# WSTL18P1.net
KiCad netlist of a schematic drawn in EAGLE
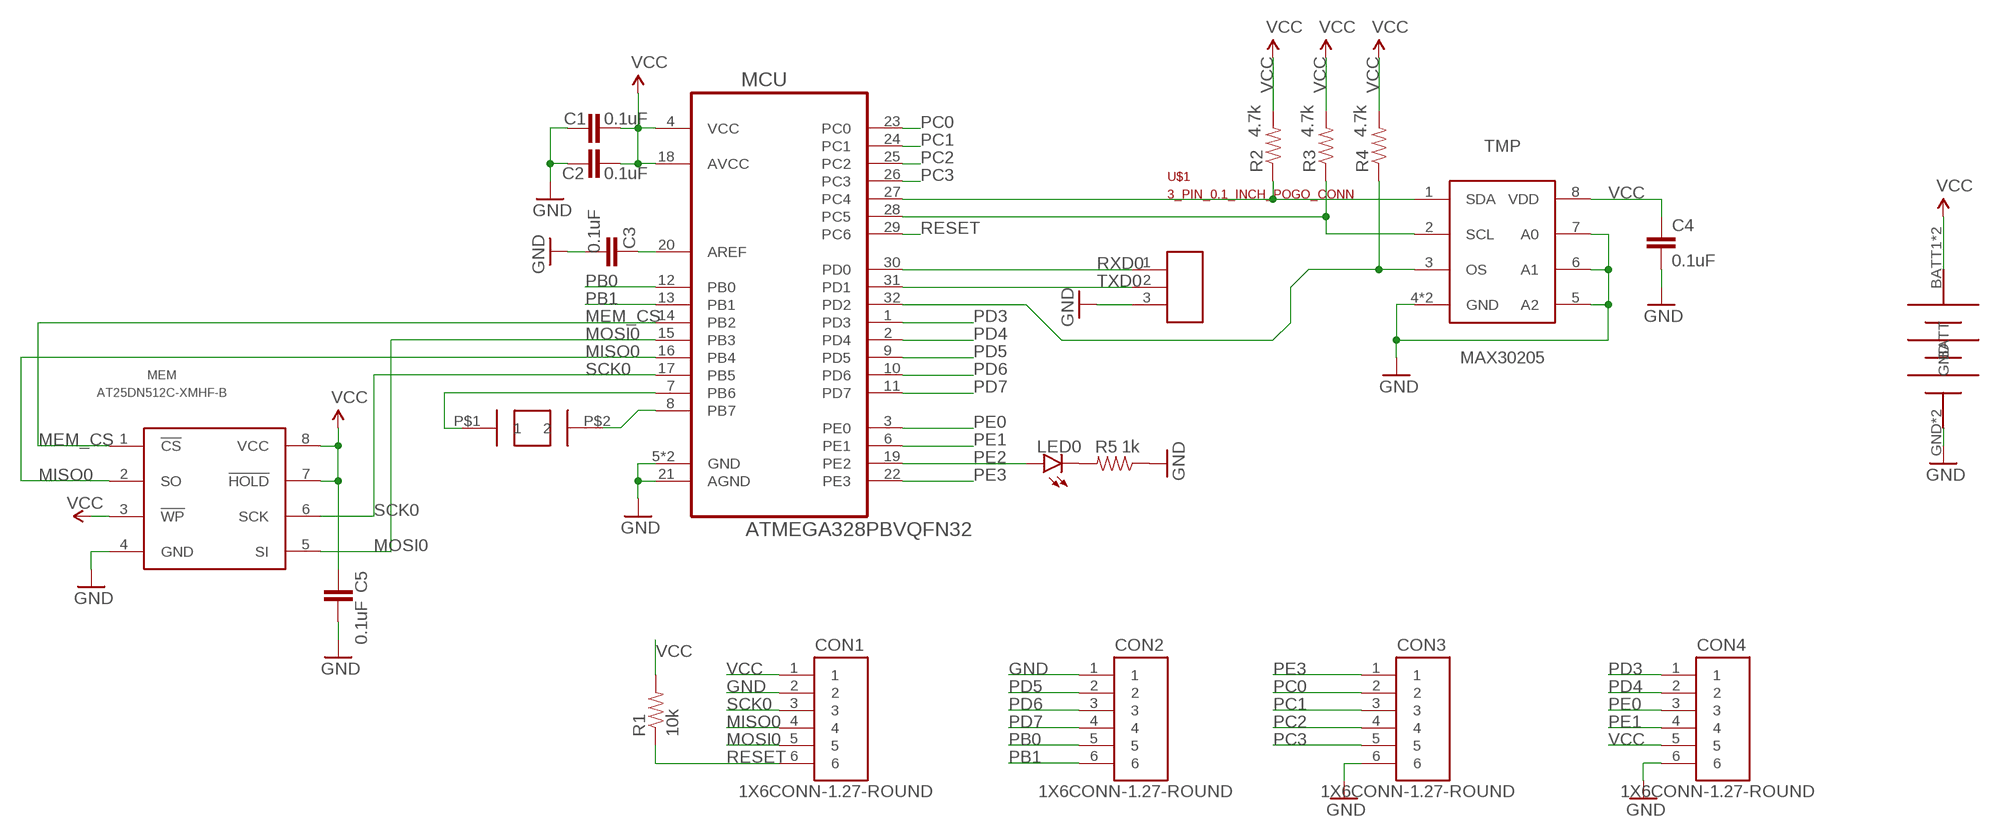
[diagram p0: schematic, sheet 1]

(export (version "E")
  (design (tool "Eeschema 10.0.6"))
  (components
    (comp (ref "BAT")
      (value "LINX-CR2032-BAT-HLD-001-M")
      (footprint "eagle-import:CR2032-LINX-M")
      (libsource (lib "eagle-import") (part "LINX-CR2032-BAT-HLD-001-M"))
    )
    (comp (ref "C1")
      (value "0.1uF")
      (footprint "eagle-import:CAP_0402")
      (libsource (lib "eagle-import") (part "CAP_0402_CERAMIC"))
    )
    (comp (ref "C2")
      (value "0.1uF")
      (footprint "eagle-import:CAP_0402")
      (libsource (lib "eagle-import") (part "CAP_0402_CERAMIC"))
    )
    (comp (ref "C3")
      (value "0.1uF")
      (footprint "eagle-import:CAP_0402")
      (libsource (lib "eagle-import") (part "CAP_0402_CERAMIC"))
    )
    (comp (ref "C4")
      (value "0.1uF")
      (footprint "eagle-import:CAP_0402")
      (libsource (lib "eagle-import") (part "CAP_0402_CERAMIC"))
    )
    (comp (ref "C5")
      (value "0.1uF")
      (footprint "eagle-import:CAP_0402")
      (libsource (lib "eagle-import") (part "CAP_0402_CERAMIC"))
    )
    (comp (ref "CON1")
      (value "1X6CONN-1.27-ROUND")
      (footprint "eagle-import:1X6_1.27_ROUND")
      (libsource (lib "eagle-import") (part "1X6CONN-1.27-ROUND"))
    )
    (comp (ref "CON2")
      (value "1X6CONN-1.27-ROUND")
      (footprint "eagle-import:1X6_1.27_ROUND")
      (libsource (lib "eagle-import") (part "1X6CONN-1.27-ROUND"))
    )
    (comp (ref "CON3")
      (value "1X6CONN-1.27-ROUND")
      (footprint "eagle-import:1X6_1.27_ROUND")
      (libsource (lib "eagle-import") (part "1X6CONN-1.27-ROUND"))
    )
    (comp (ref "CON4")
      (value "1X6CONN-1.27-ROUND")
      (footprint "eagle-import:1X6_1.27_ROUND")
      (libsource (lib "eagle-import") (part "1X6CONN-1.27-ROUND"))
    )
    (comp (ref "LED0")
      (value "LED_0402")
      (footprint "eagle-import:LED_0402")
      (libsource (lib "eagle-import") (part "LED_0402"))
    )
    (comp (ref "MCU")
      (value "ATMEGA328PBVQFN32")
      (footprint "eagle-import:ATMEGA328PB_VFQFN32")
      (libsource (lib "eagle-import") (part "ATMEGA328PBVQFN32"))
    )
    (comp (ref "MEM")
      (value "AT25DN512C-XMHF-B")
      (footprint "eagle-import:TSSSOP-8")
      (libsource (lib "eagle-import") (part "AT25DN512C-XMHF-B"))
    )
    (comp (ref "R1")
      (value "10k")
      (footprint "eagle-import:RES_0402")
      (libsource (lib "eagle-import") (part "RES_0402_CERAMIC"))
    )
    (comp (ref "R2")
      (value "4.7k")
      (footprint "eagle-import:RES_0402")
      (libsource (lib "eagle-import") (part "RES_0402_CERAMIC"))
    )
    (comp (ref "R3")
      (value "4.7k")
      (footprint "eagle-import:RES_0402")
      (libsource (lib "eagle-import") (part "RES_0402_CERAMIC"))
    )
    (comp (ref "R4")
      (value "4.7k")
      (footprint "eagle-import:RES_0402")
      (libsource (lib "eagle-import") (part "RES_0402_CERAMIC"))
    )
    (comp (ref "R5")
      (value "1k")
      (footprint "eagle-import:RES_0402")
      (libsource (lib "eagle-import") (part "RES_0402_CERAMIC"))
    )
    (comp (ref "T1")
      (value "ABS07AIG")
      (footprint "eagle-import:ABS07AIG")
      (libsource (lib "eagle-import") (part "ABS07AIG"))
    )
    (comp (ref "TMP")
      (value "MAX30205")
      (footprint "eagle-import:MAX30205_TDFN8")
      (libsource (lib "eagle-import") (part "MAX30205"))
    )
    (comp (ref "U$1")
      (value "3_PIN_0.1_INCH_POGO_CONN")
      (footprint "eagle-import:3_PIN_0.1INCH_POGO_PADS")
      (libsource (lib "eagle-import") (part "3_PIN_0.1_INCH_POGO_CONN"))
    )
  )
  (nets
    (net (code "1") (name "/MEM_CS") (class "Default")
      (node (ref "MCU") (pin "14") (pinfunction "PB2_14") (pintype "bidirectional"))
      (node (ref "MEM") (pin "1") (pinfunction "~{CS}_1") (pintype "bidirectional"))
    )
    (net (code "2") (name "/MISO0") (class "Default")
      (node (ref "CON1") (pin "4") (pinfunction "4_4") (pintype "bidirectional"))
      (node (ref "MCU") (pin "16") (pinfunction "PB4_16") (pintype "bidirectional"))
      (node (ref "MEM") (pin "2") (pinfunction "SO_2") (pintype "bidirectional"))
    )
    (net (code "3") (name "/MOSI0") (class "Default")
      (node (ref "CON1") (pin "5") (pinfunction "5_5") (pintype "bidirectional"))
      (node (ref "MCU") (pin "15") (pinfunction "PB3_15") (pintype "bidirectional"))
      (node (ref "MEM") (pin "5") (pinfunction "SI_5") (pintype "bidirectional"))
    )
    (net (code "4") (name "/PB0") (class "Default")
      (node (ref "CON2") (pin "5") (pinfunction "5_5") (pintype "bidirectional"))
      (node (ref "MCU") (pin "12") (pinfunction "PB0_12") (pintype "bidirectional"))
    )
    (net (code "5") (name "/PB1") (class "Default")
      (node (ref "CON2") (pin "6") (pinfunction "6_6") (pintype "bidirectional"))
      (node (ref "MCU") (pin "13") (pinfunction "PB1_13") (pintype "bidirectional"))
    )
    (net (code "6") (name "/PC0") (class "Default")
      (node (ref "CON3") (pin "2") (pinfunction "2_2") (pintype "bidirectional"))
      (node (ref "MCU") (pin "23") (pinfunction "PC0_23") (pintype "bidirectional"))
    )
    (net (code "7") (name "/PC1") (class "Default")
      (node (ref "CON3") (pin "3") (pinfunction "3_3") (pintype "bidirectional"))
      (node (ref "MCU") (pin "24") (pinfunction "PC1_24") (pintype "bidirectional"))
    )
    (net (code "8") (name "/PC2") (class "Default")
      (node (ref "CON3") (pin "4") (pinfunction "4_4") (pintype "bidirectional"))
      (node (ref "MCU") (pin "25") (pinfunction "PC2_25") (pintype "bidirectional"))
    )
    (net (code "9") (name "/PC3") (class "Default")
      (node (ref "CON3") (pin "5") (pinfunction "5_5") (pintype "bidirectional"))
      (node (ref "MCU") (pin "26") (pinfunction "PC3_26") (pintype "bidirectional"))
    )
    (net (code "10") (name "/PD3") (class "Default")
      (node (ref "CON4") (pin "1") (pinfunction "1_1") (pintype "bidirectional"))
      (node (ref "MCU") (pin "1") (pinfunction "PD3_1") (pintype "bidirectional"))
    )
    (net (code "11") (name "/PD4") (class "Default")
      (node (ref "CON4") (pin "2") (pinfunction "2_2") (pintype "bidirectional"))
      (node (ref "MCU") (pin "2") (pinfunction "PD4_2") (pintype "bidirectional"))
    )
    (net (code "12") (name "/PD5") (class "Default")
      (node (ref "CON2") (pin "2") (pinfunction "2_2") (pintype "bidirectional"))
      (node (ref "MCU") (pin "9") (pinfunction "PD5_9") (pintype "bidirectional"))
    )
    (net (code "13") (name "/PD6") (class "Default")
      (node (ref "CON2") (pin "3") (pinfunction "3_3") (pintype "bidirectional"))
      (node (ref "MCU") (pin "10") (pinfunction "PD6_10") (pintype "bidirectional"))
    )
    (net (code "14") (name "/PD7") (class "Default")
      (node (ref "CON2") (pin "4") (pinfunction "4_4") (pintype "bidirectional"))
      (node (ref "MCU") (pin "11") (pinfunction "PD7_11") (pintype "bidirectional"))
    )
    (net (code "15") (name "/PE0") (class "Default")
      (node (ref "CON4") (pin "3") (pinfunction "3_3") (pintype "bidirectional"))
      (node (ref "MCU") (pin "3") (pinfunction "PE0_3") (pintype "bidirectional"))
    )
    (net (code "16") (name "/PE1") (class "Default")
      (node (ref "CON4") (pin "4") (pinfunction "4_4") (pintype "bidirectional"))
      (node (ref "MCU") (pin "6") (pinfunction "PE1_6") (pintype "bidirectional"))
    )
    (net (code "17") (name "/PE2") (class "Default")
      (node (ref "LED0") (pin "ANODE") (pinfunction "A_ANODE") (pintype "passive"))
      (node (ref "MCU") (pin "19") (pinfunction "PE2_19") (pintype "bidirectional"))
    )
    (net (code "18") (name "/PE3") (class "Default")
      (node (ref "CON3") (pin "1") (pinfunction "1_1") (pintype "bidirectional"))
      (node (ref "MCU") (pin "22") (pinfunction "PE3_22") (pintype "bidirectional"))
    )
    (net (code "19") (name "/RESET") (class "Default")
      (node (ref "CON1") (pin "6") (pinfunction "6_6") (pintype "bidirectional"))
      (node (ref "MCU") (pin "29") (pinfunction "PC6_29") (pintype "bidirectional"))
      (node (ref "R1") (pin "2") (pinfunction "2_2") (pintype "passive"))
    )
    (net (code "20") (name "/RXD0") (class "Default")
      (node (ref "MCU") (pin "30") (pinfunction "PD0_30") (pintype "bidirectional"))
      (node (ref "U$1") (pin "1") (pinfunction "1_1") (pintype "bidirectional"))
    )
    (net (code "21") (name "/SCK0") (class "Default")
      (node (ref "CON1") (pin "3") (pinfunction "3_3") (pintype "bidirectional"))
      (node (ref "MCU") (pin "17") (pinfunction "PB5_17") (pintype "bidirectional"))
      (node (ref "MEM") (pin "6") (pinfunction "SCK_6") (pintype "bidirectional"))
    )
    (net (code "22") (name "/TXD0") (class "Default")
      (node (ref "MCU") (pin "31") (pinfunction "PD1_31") (pintype "bidirectional"))
      (node (ref "U$1") (pin "2") (pinfunction "2_2") (pintype "bidirectional"))
    )
    (net (code "23") (name "GND") (class "Default")
      (node (ref "BAT") (pin "GND") (pinfunction "GND_GND") (pintype "bidirectional"))
      (node (ref "BAT") (pin "GND1") (pinfunction "GND_GND1") (pintype "bidirectional"))
      (node (ref "C1") (pin "2") (pinfunction "2_2") (pintype "passive"))
      (node (ref "C2") (pin "2") (pinfunction "2_2") (pintype "passive"))
      (node (ref "C3") (pin "2") (pinfunction "2_2") (pintype "passive"))
      (node (ref "C4") (pin "2") (pinfunction "2_2") (pintype "passive"))
      (node (ref "C5") (pin "2") (pinfunction "2_2") (pintype "passive"))
      (node (ref "CON1") (pin "2") (pinfunction "2_2") (pintype "bidirectional"))
      (node (ref "CON2") (pin "1") (pinfunction "1_1") (pintype "bidirectional"))
      (node (ref "CON3") (pin "6") (pinfunction "6_6") (pintype "bidirectional"))
      (node (ref "CON4") (pin "6") (pinfunction "6_6") (pintype "bidirectional"))
      (node (ref "MCU") (pin "21") (pinfunction "AGND_21") (pintype "passive"))
      (node (ref "MCU") (pin "5") (pinfunction "GND_5") (pintype "passive"))
      (node (ref "MCU") (pin "PAD") (pinfunction "GND_PAD") (pintype "passive"))
      (node (ref "MEM") (pin "4") (pinfunction "GND_4") (pintype "bidirectional"))
      (node (ref "R5") (pin "2") (pinfunction "2_2") (pintype "passive"))
      (node (ref "TMP") (pin "4") (pinfunction "GND_4") (pintype "bidirectional"))
      (node (ref "TMP") (pin "5") (pinfunction "A2_5") (pintype "bidirectional"))
      (node (ref "TMP") (pin "6") (pinfunction "A1_6") (pintype "bidirectional"))
      (node (ref "TMP") (pin "7") (pinfunction "A0_7") (pintype "bidirectional"))
      (node (ref "TMP") (pin "PAD") (pinfunction "GND_PAD") (pintype "bidirectional"))
      (node (ref "U$1") (pin "3") (pinfunction "3_3") (pintype "bidirectional"))
    )
    (net (code "24") (name "Net-(LED0-C)") (class "Default")
      (node (ref "LED0") (pin "CATHODE") (pinfunction "C_CATHODE") (pintype "passive"))
      (node (ref "R5") (pin "1") (pinfunction "1_1") (pintype "passive"))
    )
    (net (code "25") (name "Net-(MCU-AREF)") (class "Default")
      (node (ref "C3") (pin "1") (pinfunction "1_1") (pintype "passive"))
      (node (ref "MCU") (pin "20") (pinfunction "AREF_20") (pintype "input"))
    )
    (net (code "26") (name "Net-(MCU-PB6)") (class "Default")
      (node (ref "MCU") (pin "7") (pinfunction "PB6_7") (pintype "bidirectional"))
      (node (ref "T1") (pin "P$1") (pinfunction "1_P$1") (pintype "bidirectional"))
    )
    (net (code "27") (name "Net-(MCU-PB7)") (class "Default")
      (node (ref "MCU") (pin "8") (pinfunction "PB7_8") (pintype "bidirectional"))
      (node (ref "T1") (pin "P$2") (pinfunction "2_P$2") (pintype "bidirectional"))
    )
    (net (code "28") (name "Net-(MCU-PC4)") (class "Default")
      (node (ref "MCU") (pin "27") (pinfunction "PC4_27") (pintype "bidirectional"))
      (node (ref "R2") (pin "2") (pinfunction "2_2") (pintype "passive"))
      (node (ref "TMP") (pin "1") (pinfunction "SDA_1") (pintype "bidirectional"))
    )
    (net (code "29") (name "Net-(MCU-PC5)") (class "Default")
      (node (ref "MCU") (pin "28") (pinfunction "PC5_28") (pintype "bidirectional"))
      (node (ref "R3") (pin "2") (pinfunction "2_2") (pintype "passive"))
      (node (ref "TMP") (pin "2") (pinfunction "SCL_2") (pintype "bidirectional"))
    )
    (net (code "30") (name "Net-(MCU-PD2)") (class "Default")
      (node (ref "MCU") (pin "32") (pinfunction "PD2_32") (pintype "bidirectional"))
      (node (ref "R4") (pin "2") (pinfunction "2_2") (pintype "passive"))
      (node (ref "TMP") (pin "3") (pinfunction "OS_3") (pintype "bidirectional"))
    )
    (net (code "31") (name "VCC") (class "Default")
      (node (ref "BAT") (pin "BATT1") (pinfunction "BATT_BATT1") (pintype "bidirectional"))
      (node (ref "BAT") (pin "BATT2") (pinfunction "BATT_BATT2") (pintype "bidirectional"))
      (node (ref "C1") (pin "1") (pinfunction "1_1") (pintype "passive"))
      (node (ref "C2") (pin "1") (pinfunction "1_1") (pintype "passive"))
      (node (ref "C4") (pin "1") (pinfunction "1_1") (pintype "passive"))
      (node (ref "C5") (pin "1") (pinfunction "1_1") (pintype "passive"))
      (node (ref "CON1") (pin "1") (pinfunction "1_1") (pintype "bidirectional"))
      (node (ref "CON4") (pin "5") (pinfunction "5_5") (pintype "bidirectional"))
      (node (ref "MCU") (pin "18") (pinfunction "AVCC_18") (pintype "power_in"))
      (node (ref "MCU") (pin "4") (pinfunction "VCC_4") (pintype "power_in"))
      (node (ref "MEM") (pin "3") (pinfunction "~{WP}_3") (pintype "bidirectional"))
      (node (ref "MEM") (pin "7") (pinfunction "~{HOLD}_7") (pintype "bidirectional"))
      (node (ref "MEM") (pin "8") (pinfunction "VCC_8") (pintype "bidirectional"))
      (node (ref "R1") (pin "1") (pinfunction "1_1") (pintype "passive"))
      (node (ref "R2") (pin "1") (pinfunction "1_1") (pintype "passive"))
      (node (ref "R3") (pin "1") (pinfunction "1_1") (pintype "passive"))
      (node (ref "R4") (pin "1") (pinfunction "1_1") (pintype "passive"))
      (node (ref "TMP") (pin "8") (pinfunction "VDD_8") (pintype "bidirectional"))
    )
  )
)
